# STM32H743.net
KiCad netlist of a schematic drawn in Altium Designer
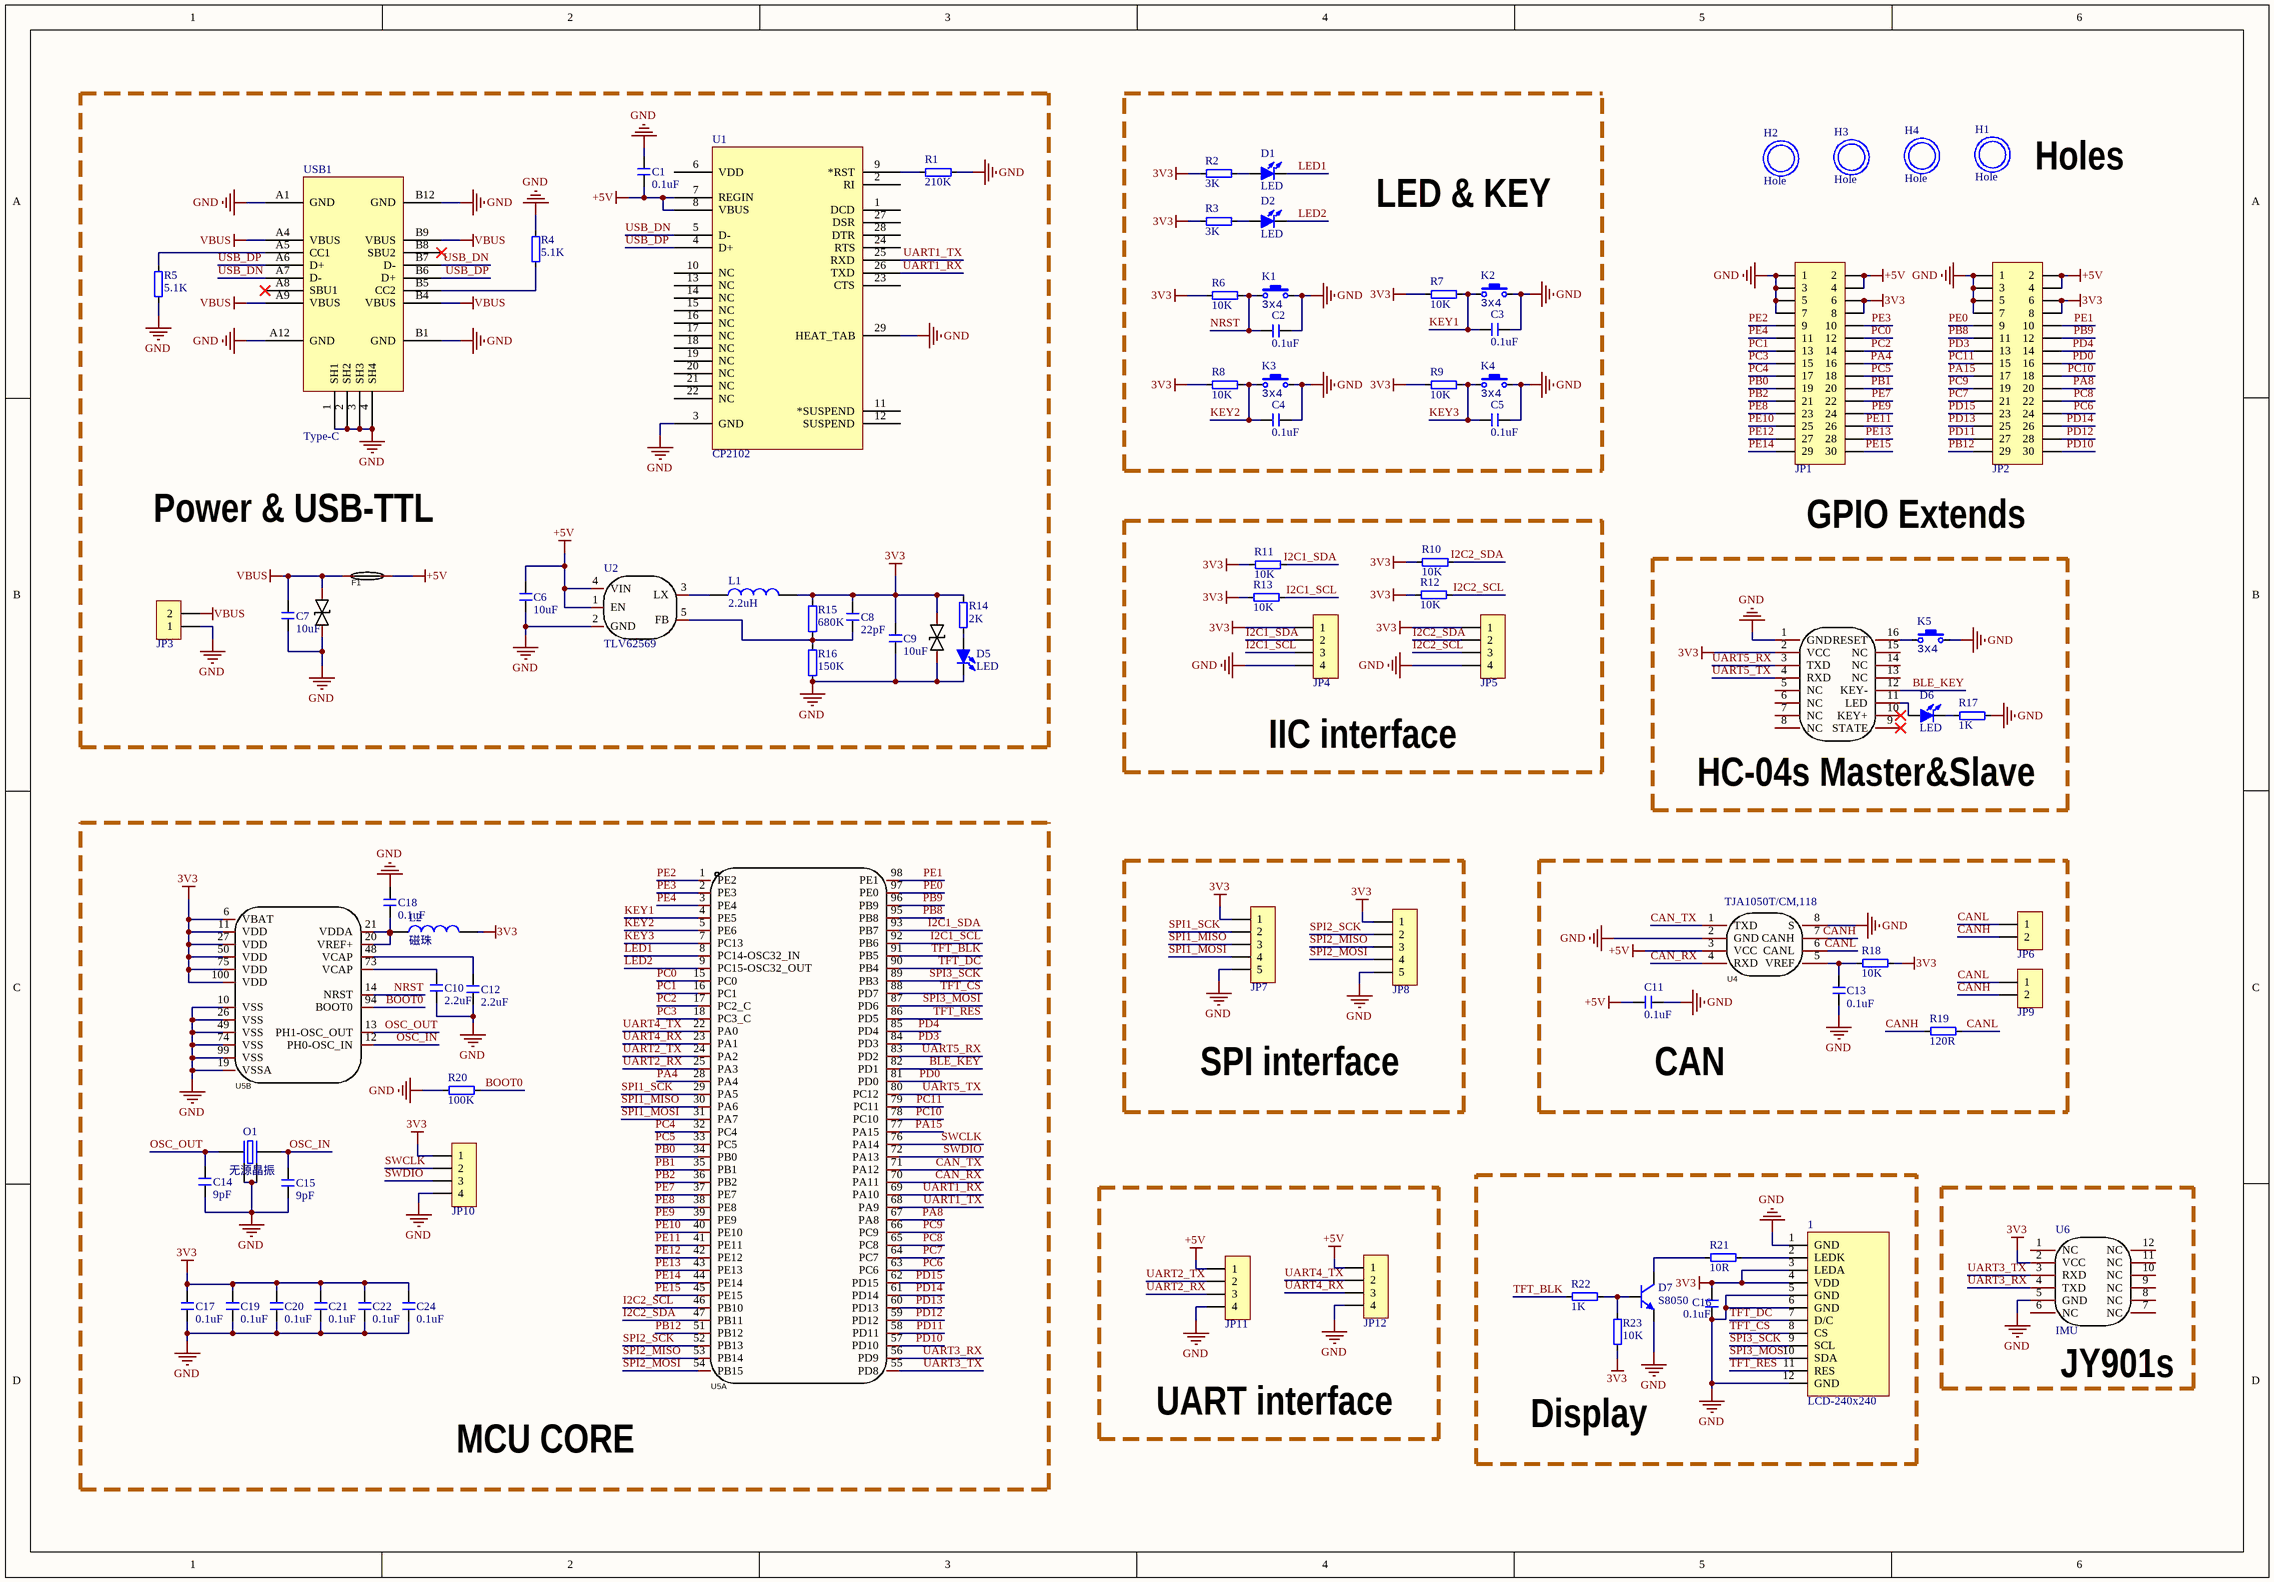
[diagram p0: STM32H743_原理图.SchDoc]

(export (version "E")
  (design (tool "Eeschema 10.0.6"))
  (components
    (comp (ref "1")
      (value "LCD-240x240")
      (footprint "LCD-240x240-NoHole")
      (description "显示屏")
      (libsource (lib "STM32H743原理图库") (part "LCD-240x240"))
    )
    (comp (ref "C1") (value "0.1uF") (footprint "CAP_0402") (libsource (lib "IntLib") (part "Capacitor")))
    (comp (ref "C2") (value "0.1uF") (footprint "CAP_0402") (libsource (lib "IntLib") (part "Capacitor")))
    (comp (ref "C3") (value "0.1uF") (footprint "CAP_0402") (libsource (lib "IntLib") (part "Capacitor")))
    (comp (ref "C4") (value "0.1uF") (footprint "CAP_0402") (libsource (lib "IntLib") (part "Capacitor")))
    (comp (ref "C5") (value "0.1uF") (footprint "CAP_0402") (libsource (lib "IntLib") (part "Capacitor")))
    (comp (ref "C6") (value "10uF") (footprint "CAP_0402") (libsource (lib "IntLib") (part "Capacitor")))
    (comp (ref "C7") (value "10uF") (footprint "CAP_0402") (libsource (lib "IntLib") (part "Capacitor")))
    (comp (ref "C8") (value "22pF") (footprint "CAP_0402") (libsource (lib "IntLib") (part "Capacitor")))
    (comp (ref "C9") (value "10uF") (footprint "CAP_0402") (libsource (lib "IntLib") (part "Capacitor")))
    (comp (ref "C10") (value "2.2uF") (footprint "CAP_0402") (libsource (lib "IntLib") (part "Capacitor")))
    (comp (ref "C11") (value "0.1uF") (footprint "CAP_0402") (libsource (lib "IntLib") (part "Capacitor")))
    (comp (ref "C12") (value "2.2uF") (footprint "CAP_0402") (libsource (lib "IntLib") (part "Capacitor")))
    (comp (ref "C13") (value "0.1uF") (footprint "CAP_0402") (libsource (lib "IntLib") (part "Capacitor")))
    (comp (ref "C14") (value "9pF") (footprint "CAP_0402") (libsource (lib "IntLib") (part "Capacitor")))
    (comp (ref "C15") (value "9pF") (footprint "CAP_0402") (libsource (lib "IntLib") (part "Capacitor")))
    (comp (ref "C16") (value "0.1uF") (footprint "CAP_0402") (libsource (lib "IntLib") (part "Capacitor")))
    (comp (ref "C17") (value "0.1uF") (footprint "CAP_0402") (libsource (lib "IntLib") (part "Capacitor")))
    (comp (ref "C18") (value "0.1uF") (footprint "CAP_0402") (libsource (lib "IntLib") (part "Capacitor")))
    (comp (ref "C19") (value "0.1uF") (footprint "CAP_0402") (libsource (lib "IntLib") (part "Capacitor")))
    (comp (ref "C20") (value "0.1uF") (footprint "CAP_0402") (libsource (lib "IntLib") (part "Capacitor")))
    (comp (ref "C21") (value "0.1uF") (footprint "CAP_0402") (libsource (lib "IntLib") (part "Capacitor")))
    (comp (ref "C22") (value "0.1uF") (footprint "CAP_0402") (libsource (lib "IntLib") (part "Capacitor")))
    (comp (ref "C24") (value "0.1uF") (footprint "CAP_0402") (libsource (lib "IntLib") (part "Capacitor")))
    (comp (ref "D1") (value "LED") (footprint "LED_0402_RED") (libsource (lib "IntLib") (part "LED")))
    (comp (ref "D2") (value "LED") (footprint "LED_0402_RED") (libsource (lib "IntLib") (part "LED")))
    (comp (ref "D3")
      (value "LESD3Z5.0CMT1G")
      (footprint "SOD-323")
      (fields (field (name "MANUFACTURER") "LRC(乐山无线电)"))
      (libsource (lib "STM32H743原理图库") (part "LESD3Z5.0CMT1G"))
    )
    (comp (ref "D4")
      (value "LESD3Z5.0CMT1G")
      (footprint "SOD-323")
      (fields (field (name "MANUFACTURER") "LRC(乐山无线电)"))
      (libsource (lib "STM32H743原理图库") (part "LESD3Z5.0CMT1G"))
    )
    (comp (ref "D5") (value "LED") (footprint "LED_0402_RED") (libsource (lib "IntLib") (part "LED")))
    (comp (ref "D6") (value "LED") (footprint "LED_0402_RED") (libsource (lib "IntLib") (part "LED")))
    (comp (ref "D7") (value "S8050") (footprint "SOT23-3L") (libsource (lib "IntLib") (part "三极管-NPN")))
    (comp (ref "F1")
      (value "S0603-F-2.0A")
      (footprint "R 0603")
      (fields (field (name "MANUFACTURER") "SART(萨特)"))
      (libsource (lib "STM32H743原理图库") (part "S0603-F-2.0A"))
    )
    (comp (ref "H1") (value "Hole") (footprint "Hole") (libsource (lib "IntLib") (part "Hole")))
    (comp (ref "H2") (value "Hole") (footprint "Hole") (libsource (lib "IntLib") (part "Hole")))
    (comp (ref "H3") (value "Hole") (footprint "Hole") (libsource (lib "IntLib") (part "Hole")))
    (comp (ref "H4") (value "Hole") (footprint "Hole") (libsource (lib "IntLib") (part "Hole")))
    (comp (ref "JP1")
      (value "Header 2X11")
      (footprint "HDR2.54-LI-2x15P")
      (description "15*2P接插件")
      (fields (field (name "版权归属") "源创客"))
      (libsource (lib "STM32H743原理图库") (part "Header 15X2"))
    )
    (comp (ref "JP2")
      (value "Header 2X11")
      (footprint "HDR2.54-LI-2x15P")
      (description "15*2P接插件")
      (fields (field (name "版权归属") "源创客"))
      (libsource (lib "STM32H743原理图库") (part "Header 15X2"))
    )
    (comp (ref "JP3")
      (value "HDR-1X2")
      (footprint "HDR2.54-LI-2P")
      (description "2P接插件")
      (fields (field (name "版权归属") "源创客"))
      (libsource (lib "") (part "Header 2_1"))
    )
    (comp (ref "JP4")
      (value "HDR-1X4")
      (footprint "MX 1.25-WS-4P")
      (description "4P接插件")
      (fields (field (name "版权归属") "源创客"))
      (libsource (lib "STM32H743原理图库") (part "Header 4"))
    )
    (comp (ref "JP5")
      (value "HDR-1X4")
      (footprint "MX 1.25-WS-4P")
      (description "4P接插件")
      (fields (field (name "版权归属") "源创客"))
      (libsource (lib "STM32H743原理图库") (part "Header 4"))
    )
    (comp (ref "JP6")
      (value "HDR-1X2")
      (footprint "GH1.25-WT-2P")
      (description "2P接插件")
      (fields (field (name "版权归属") "源创客"))
      (libsource (lib "STM32H743原理图库") (part "Header 2"))
    )
    (comp (ref "JP7")
      (value "HDR-1X5")
      (footprint "MX 1.25-WS-5P")
      (description "5P接插件")
      (fields (field (name "版权归属") "源创客"))
      (libsource (lib "STM32H743原理图库") (part "Header 5"))
    )
    (comp (ref "JP8")
      (value "HDR-1X5")
      (footprint "MX 1.25-WS-5P")
      (description "5P接插件")
      (fields (field (name "版权归属") "源创客"))
      (libsource (lib "STM32H743原理图库") (part "Header 5"))
    )
    (comp (ref "JP9")
      (value "HDR-1X2")
      (footprint "GH1.25-WT-2P")
      (description "2P接插件")
      (fields (field (name "版权归属") "源创客"))
      (libsource (lib "STM32H743原理图库") (part "Header 2"))
    )
    (comp (ref "JP10")
      (value "HDR-1X4")
      (footprint "MX 1.25-WS-4P")
      (description "4P接插件")
      (fields (field (name "版权归属") "源创客"))
      (libsource (lib "STM32H743原理图库") (part "Header 4"))
    )
    (comp (ref "JP11")
      (value "HDR-1X4")
      (footprint "MX 1.25-WS-4P")
      (description "4P接插件")
      (fields (field (name "版权归属") "源创客"))
      (libsource (lib "STM32H743原理图库") (part "Header 4"))
    )
    (comp (ref "JP12")
      (value "HDR-1X4")
      (footprint "MX 1.25-WS-4P")
      (description "4P接插件")
      (fields (field (name "版权归属") "源创客"))
      (libsource (lib "STM32H743原理图库") (part "Header 4"))
    )
    (comp (ref "K1")
      (value "3x4")
      (footprint "KEY")
      (description "Button")
      (fields (field (name "Comment") "TACT 2P"))
      (libsource (lib "STM32H743原理图库") (part "ButtonTACT_3x4x2_180"))
    )
    (comp (ref "K2")
      (value "3x4")
      (footprint "KEY")
      (description "Button")
      (fields (field (name "Comment") "TACT 2P"))
      (libsource (lib "STM32H743原理图库") (part "ButtonTACT_3x4x2_180"))
    )
    (comp (ref "K3")
      (value "3x4")
      (footprint "KEY")
      (description "Button")
      (fields (field (name "Comment") "TACT 2P"))
      (libsource (lib "STM32H743原理图库") (part "ButtonTACT_3x4x2_180"))
    )
    (comp (ref "K4")
      (value "3x4")
      (footprint "KEY")
      (description "Button")
      (fields (field (name "Comment") "TACT 2P"))
      (libsource (lib "STM32H743原理图库") (part "ButtonTACT_3x4x2_180"))
    )
    (comp (ref "K5")
      (value "3x4")
      (footprint "KEY")
      (description "Button")
      (fields (field (name "Comment") "TACT 2P"))
      (libsource (lib "STM32H743原理图库") (part "ButtonTACT_3x4x2_180"))
    )
    (comp (ref "L1") (value "2.2uH") (footprint "2520-L") (libsource (lib "IntLib") (part "Inductance")))
    (comp (ref "L2") (value "磁珠") (footprint "L 0603") (libsource (lib "IntLib") (part "Inductance")))
    (comp (ref "O1") (value "无源晶振") (footprint "OSC 3225-4P") (libsource (lib "STM32H743原理图库") (part "无源晶振")))
    (comp (ref "R1") (value "210K") (footprint "RES_0402") (libsource (lib "IntLib") (part "Resistor")))
    (comp (ref "R2") (value "3K") (footprint "RES_0402") (libsource (lib "IntLib") (part "Resistor")))
    (comp (ref "R3") (value "3K") (footprint "RES_0402") (libsource (lib "IntLib") (part "Resistor")))
    (comp (ref "R4") (value "5.1K") (footprint "RES_0402") (libsource (lib "IntLib") (part "Resistor")))
    (comp (ref "R5") (value "5.1K") (footprint "RES_0402") (libsource (lib "IntLib") (part "Resistor")))
    (comp (ref "R6") (value "10K") (footprint "RES_0402") (libsource (lib "IntLib") (part "Resistor")))
    (comp (ref "R7") (value "10K") (footprint "RES_0402") (libsource (lib "IntLib") (part "Resistor")))
    (comp (ref "R8") (value "10K") (footprint "RES_0402") (libsource (lib "IntLib") (part "Resistor")))
    (comp (ref "R9") (value "10K") (footprint "RES_0402") (libsource (lib "IntLib") (part "Resistor")))
    (comp (ref "R10") (value "10K") (footprint "RES_0402") (libsource (lib "IntLib") (part "Resistor")))
    (comp (ref "R11") (value "10K") (footprint "RES_0402") (libsource (lib "IntLib") (part "Resistor")))
    (comp (ref "R12") (value "10K") (footprint "RES_0402") (libsource (lib "IntLib") (part "Resistor")))
    (comp (ref "R13") (value "10K") (footprint "RES_0402") (libsource (lib "IntLib") (part "Resistor")))
    (comp (ref "R14") (value "2K") (footprint "RES_0402") (libsource (lib "IntLib") (part "Resistor")))
    (comp (ref "R15") (value "680K") (footprint "RES_0402") (libsource (lib "IntLib") (part "Resistor")))
    (comp (ref "R16") (value "150K") (footprint "RES_0402") (libsource (lib "IntLib") (part "Resistor")))
    (comp (ref "R17") (value "1K") (footprint "RES_0402") (libsource (lib "IntLib") (part "Resistor")))
    (comp (ref "R18") (value "10K") (footprint "RES_0402") (libsource (lib "IntLib") (part "Resistor")))
    (comp (ref "R19") (value "120R") (footprint "RES_0402") (libsource (lib "IntLib") (part "Resistor")))
    (comp (ref "R20") (value "100K") (footprint "RES_0402") (libsource (lib "IntLib") (part "Resistor")))
    (comp (ref "R21") (value "10R") (footprint "RES_0402") (libsource (lib "IntLib") (part "Resistor")))
    (comp (ref "R22") (value "1K") (footprint "RES_0402") (libsource (lib "IntLib") (part "Resistor")))
    (comp (ref "R23") (value "10K") (footprint "RES_0402") (libsource (lib "IntLib") (part "Resistor")))
    (comp (ref "U1")
      (value "CP2102")
      (footprint "QFN-28")
      (description "USB转TTL")
      (libsource (lib "STM32H743原理图库") (part "CP2102"))
    )
    (comp (ref "U2")
      (value "TLV62569")
      (footprint "SOT23-5N")
      (libsource (lib "STM32H743原理图库") (part "TLV62569"))
    )
    (comp (ref "U3")
      (value "TJA1050T/CM,118")
      (footprint "HC-04-S")
      (fields (field (name "MANUFACTURER") "NXP(恩智浦)"))
      (libsource (lib "STM32H743原理图库") (part "HC-04-S"))
    )
    (comp (ref "U4")
      (value "TJA1050T/CM,118")
      (footprint "SOP8")
      (fields (field (name "MANUFACTURER") "NXP(恩智浦)"))
      (libsource (lib "STM32H743原理图库") (part "TJA1050T/CM,118"))
    )
    (comp (ref "U5")
      (value "STM32H743VIT6_C114409")
      (footprint "LQFP100-14*14")
      (fields (field (name "MANUFACTURER") "ST(意法半导体)") (field (name "MANUFACTURER PART") "STM32H743VIT6"))
      (libsource (lib "STM32H743原理图库") (part "STM32H743VIT6_C114409"))
    )
    (comp (ref "U6") (value "IMU") (footprint "IMU") (libsource (lib "STM32H743原理图库") (part "IMU")))
    (comp (ref "USB1")
      (value "Type-C")
      (footprint "Type-C-TOP")
      (libsource (lib "STM32H743原理图库") (part "USB-Type-C-TOP"))
    )
  )
  (nets
    (net (code "1") (name "+5V") (class "Default")
      (node (ref "C1") (pin "1") (pinfunction "1_1") (pintype "passive"))
      (node (ref "C11") (pin "2") (pinfunction "2_2") (pintype "passive"))
      (node (ref "C6") (pin "2") (pinfunction "2_2") (pintype "passive"))
      (node (ref "F1") (pin "2") (pinfunction "2_2") (pintype "passive"))
      (node (ref "JP1") (pin "2") (pinfunction "2_2") (pintype "passive"))
      (node (ref "JP1") (pin "4") (pinfunction "4_4") (pintype "passive"))
      (node (ref "JP11") (pin "1") (pinfunction "1_1") (pintype "passive"))
      (node (ref "JP12") (pin "1") (pinfunction "1_1") (pintype "passive"))
      (node (ref "JP2") (pin "2") (pinfunction "2_2") (pintype "passive"))
      (node (ref "JP2") (pin "4") (pinfunction "4_4") (pintype "passive"))
      (node (ref "U1") (pin "7") (pinfunction "REGIN_7") (pintype "passive"))
      (node (ref "U1") (pin "8") (pinfunction "VBUS_8") (pintype "passive"))
      (node (ref "U2") (pin "1") (pinfunction "EN_1") (pintype "passive"))
      (node (ref "U2") (pin "4") (pinfunction "VIN_4") (pintype "passive"))
      (node (ref "U4") (pin "3") (pinfunction "VCC_3") (pintype "passive"))
    )
    (net (code "2") (name "/BLE_KEY") (class "Default")
      (node (ref "U3") (pin "12") (pinfunction "KEY-_12") (pintype "passive"))
      (node (ref "U5") (pin "82") (pinfunction "PD1_82") (pintype "passive"))
    )
    (net (code "3") (name "/BOOT0") (class "Default")
      (node (ref "R20") (pin "1") (pinfunction "1_1") (pintype "passive"))
      (node (ref "U5") (pin "94") (pinfunction "BOOT0_94") (pintype "passive"))
    )
    (net (code "4") (name "/CANH") (class "Default")
      (node (ref "JP6") (pin "2") (pinfunction "2_2") (pintype "passive"))
      (node (ref "JP9") (pin "2") (pinfunction "2_2") (pintype "passive"))
      (node (ref "R19") (pin "2") (pinfunction "2_2") (pintype "passive"))
      (node (ref "U4") (pin "7") (pinfunction "CANH_7") (pintype "passive"))
    )
    (net (code "5") (name "/CANL") (class "Default")
      (node (ref "JP6") (pin "1") (pinfunction "1_1") (pintype "passive"))
      (node (ref "JP9") (pin "1") (pinfunction "1_1") (pintype "passive"))
      (node (ref "R19") (pin "1") (pinfunction "1_1") (pintype "passive"))
      (node (ref "U4") (pin "6") (pinfunction "CANL_6") (pintype "passive"))
    )
    (net (code "6") (name "/CAN_RX") (class "Default")
      (node (ref "U4") (pin "4") (pinfunction "RXD_4") (pintype "passive"))
      (node (ref "U5") (pin "70") (pinfunction "PA11_70") (pintype "passive"))
    )
    (net (code "7") (name "/CAN_TX") (class "Default")
      (node (ref "U4") (pin "1") (pinfunction "TXD_1") (pintype "passive"))
      (node (ref "U5") (pin "71") (pinfunction "PA12_71") (pintype "passive"))
    )
    (net (code "8") (name "/I2C1_SCL") (class "Default")
      (node (ref "JP4") (pin "3") (pinfunction "3_3") (pintype "passive"))
      (node (ref "R13") (pin "1") (pinfunction "1_1") (pintype "passive"))
      (node (ref "U5") (pin "92") (pinfunction "PB6_92") (pintype "passive"))
    )
    (net (code "9") (name "/I2C1_SDA") (class "Default")
      (node (ref "JP4") (pin "2") (pinfunction "2_2") (pintype "passive"))
      (node (ref "R11") (pin "1") (pinfunction "1_1") (pintype "passive"))
      (node (ref "U5") (pin "93") (pinfunction "PB7_93") (pintype "passive"))
    )
    (net (code "10") (name "/I2C2_SCL") (class "Default")
      (node (ref "JP5") (pin "3") (pinfunction "3_3") (pintype "passive"))
      (node (ref "R12") (pin "1") (pinfunction "1_1") (pintype "passive"))
      (node (ref "U5") (pin "46") (pinfunction "PB10_46") (pintype "passive"))
    )
    (net (code "11") (name "/I2C2_SDA") (class "Default")
      (node (ref "JP5") (pin "2") (pinfunction "2_2") (pintype "passive"))
      (node (ref "R10") (pin "1") (pinfunction "1_1") (pintype "passive"))
      (node (ref "U5") (pin "47") (pinfunction "PB11_47") (pintype "passive"))
    )
    (net (code "12") (name "/KEY1") (class "Default")
      (node (ref "C3") (pin "2") (pinfunction "2_2") (pintype "passive"))
      (node (ref "K2") (pin "1") (pinfunction "1_1") (pintype "passive"))
      (node (ref "R7") (pin "1") (pinfunction "1_1") (pintype "passive"))
      (node (ref "U5") (pin "4") (pinfunction "PE5_4") (pintype "passive"))
    )
    (net (code "13") (name "/KEY2") (class "Default")
      (node (ref "C4") (pin "2") (pinfunction "2_2") (pintype "passive"))
      (node (ref "K3") (pin "1") (pinfunction "1_1") (pintype "passive"))
      (node (ref "R8") (pin "1") (pinfunction "1_1") (pintype "passive"))
      (node (ref "U5") (pin "5") (pinfunction "PE6_5") (pintype "passive"))
    )
    (net (code "14") (name "/KEY3") (class "Default")
      (node (ref "C5") (pin "2") (pinfunction "2_2") (pintype "passive"))
      (node (ref "K4") (pin "1") (pinfunction "1_1") (pintype "passive"))
      (node (ref "R9") (pin "1") (pinfunction "1_1") (pintype "passive"))
      (node (ref "U5") (pin "7") (pinfunction "PC13_7") (pintype "passive"))
    )
    (net (code "15") (name "/LED1") (class "Default")
      (node (ref "D1") (pin "2") (pinfunction "K_2") (pintype "passive"))
      (node (ref "U5") (pin "8") (pinfunction "PC14-OSC32_IN_8") (pintype "passive"))
    )
    (net (code "16") (name "/LED2") (class "Default")
      (node (ref "D2") (pin "2") (pinfunction "K_2") (pintype "passive"))
      (node (ref "U5") (pin "9") (pinfunction "PC15-OSC32_OUT_9") (pintype "passive"))
    )
    (net (code "17") (name "/NRST") (class "Default")
      (node (ref "C2") (pin "2") (pinfunction "2_2") (pintype "passive"))
      (node (ref "K1") (pin "1") (pinfunction "1_1") (pintype "passive"))
      (node (ref "R6") (pin "1") (pinfunction "1_1") (pintype "passive"))
      (node (ref "U5") (pin "14") (pinfunction "NRST_14") (pintype "passive"))
    )
    (net (code "18") (name "/OSC_IN") (class "Default")
      (node (ref "C15") (pin "2") (pinfunction "2_2") (pintype "passive"))
      (node (ref "O1") (pin "3") (pinfunction "3_3") (pintype "passive"))
      (node (ref "U5") (pin "12") (pinfunction "PH0-OSC_IN_12") (pintype "passive"))
    )
    (net (code "19") (name "/OSC_OUT") (class "Default")
      (node (ref "C14") (pin "2") (pinfunction "2_2") (pintype "passive"))
      (node (ref "O1") (pin "1") (pinfunction "1_1") (pintype "passive"))
      (node (ref "U5") (pin "13") (pinfunction "PH1-OSC_OUT_13") (pintype "passive"))
    )
    (net (code "20") (name "/PA4") (class "Default")
      (node (ref "JP1") (pin "16") (pinfunction "16_16") (pintype "passive"))
      (node (ref "U5") (pin "28") (pinfunction "PA4_28") (pintype "passive"))
    )
    (net (code "21") (name "/PA8") (class "Default")
      (node (ref "JP2") (pin "20") (pinfunction "20_20") (pintype "passive"))
      (node (ref "U5") (pin "67") (pinfunction "PA8_67") (pintype "passive"))
    )
    (net (code "22") (name "/PA15") (class "Default")
      (node (ref "JP2") (pin "17") (pinfunction "17_17") (pintype "passive"))
      (node (ref "U5") (pin "77") (pinfunction "PA15_77") (pintype "passive"))
    )
    (net (code "23") (name "/PB0") (class "Default")
      (node (ref "JP1") (pin "19") (pinfunction "19_19") (pintype "passive"))
      (node (ref "U5") (pin "34") (pinfunction "PB0_34") (pintype "passive"))
    )
    (net (code "24") (name "/PB1") (class "Default")
      (node (ref "JP1") (pin "20") (pinfunction "20_20") (pintype "passive"))
      (node (ref "U5") (pin "35") (pinfunction "PB1_35") (pintype "passive"))
    )
    (net (code "25") (name "/PB2") (class "Default")
      (node (ref "JP1") (pin "21") (pinfunction "21_21") (pintype "passive"))
      (node (ref "U5") (pin "36") (pinfunction "PB2_36") (pintype "passive"))
    )
    (net (code "26") (name "/PB8") (class "Default")
      (node (ref "JP2") (pin "11") (pinfunction "11_11") (pintype "passive"))
      (node (ref "U5") (pin "95") (pinfunction "PB8_95") (pintype "passive"))
    )
    (net (code "27") (name "/PB9") (class "Default")
      (node (ref "JP2") (pin "12") (pinfunction "12_12") (pintype "passive"))
      (node (ref "U5") (pin "96") (pinfunction "PB9_96") (pintype "passive"))
    )
    (net (code "28") (name "/PB12") (class "Default")
      (node (ref "JP2") (pin "29") (pinfunction "29_29") (pintype "passive"))
      (node (ref "U5") (pin "51") (pinfunction "PB12_51") (pintype "passive"))
    )
    (net (code "29") (name "/PC0") (class "Default")
      (node (ref "JP1") (pin "12") (pinfunction "12_12") (pintype "passive"))
      (node (ref "U5") (pin "15") (pinfunction "PC0_15") (pintype "passive"))
    )
    (net (code "30") (name "/PC1") (class "Default")
      (node (ref "JP1") (pin "13") (pinfunction "13_13") (pintype "passive"))
      (node (ref "U5") (pin "16") (pinfunction "PC1_16") (pintype "passive"))
    )
    (net (code "31") (name "/PC2") (class "Default")
      (node (ref "JP1") (pin "14") (pinfunction "14_14") (pintype "passive"))
      (node (ref "U5") (pin "17") (pinfunction "PC2_C_17") (pintype "passive"))
    )
    (net (code "32") (name "/PC3") (class "Default")
      (node (ref "JP1") (pin "15") (pinfunction "15_15") (pintype "passive"))
      (node (ref "U5") (pin "18") (pinfunction "PC3_C_18") (pintype "passive"))
    )
    (net (code "33") (name "/PC4") (class "Default")
      (node (ref "JP1") (pin "17") (pinfunction "17_17") (pintype "passive"))
      (node (ref "U5") (pin "32") (pinfunction "PC4_32") (pintype "passive"))
    )
    (net (code "34") (name "/PC5") (class "Default")
      (node (ref "JP1") (pin "18") (pinfunction "18_18") (pintype "passive"))
      (node (ref "U5") (pin "33") (pinfunction "PC5_33") (pintype "passive"))
    )
    (net (code "35") (name "/PC6") (class "Default")
      (node (ref "JP2") (pin "24") (pinfunction "24_24") (pintype "passive"))
      (node (ref "U5") (pin "63") (pinfunction "PC6_63") (pintype "passive"))
    )
    (net (code "36") (name "/PC7") (class "Default")
      (node (ref "JP2") (pin "21") (pinfunction "21_21") (pintype "passive"))
      (node (ref "U5") (pin "64") (pinfunction "PC7_64") (pintype "passive"))
    )
    (net (code "37") (name "/PC8") (class "Default")
      (node (ref "JP2") (pin "22") (pinfunction "22_22") (pintype "passive"))
      (node (ref "U5") (pin "65") (pinfunction "PC8_65") (pintype "passive"))
    )
    (net (code "38") (name "/PC9") (class "Default")
      (node (ref "JP2") (pin "19") (pinfunction "19_19") (pintype "passive"))
      (node (ref "U5") (pin "66") (pinfunction "PC9_66") (pintype "passive"))
    )
    (net (code "39") (name "/PC10") (class "Default")
      (node (ref "JP2") (pin "18") (pinfunction "18_18") (pintype "passive"))
      (node (ref "U5") (pin "78") (pinfunction "PC10_78") (pintype "passive"))
    )
    (net (code "40") (name "/PC11") (class "Default")
      (node (ref "JP2") (pin "15") (pinfunction "15_15") (pintype "passive"))
      (node (ref "U5") (pin "79") (pinfunction "PC11_79") (pintype "passive"))
    )
    (net (code "41") (name "/PD0") (class "Default")
      (node (ref "JP2") (pin "16") (pinfunction "16_16") (pintype "passive"))
      (node (ref "U5") (pin "81") (pinfunction "PD0_81") (pintype "passive"))
    )
    (net (code "42") (name "/PD3") (class "Default")
      (node (ref "JP2") (pin "13") (pinfunction "13_13") (pintype "passive"))
      (node (ref "U5") (pin "84") (pinfunction "PD3_84") (pintype "passive"))
    )
    (net (code "43") (name "/PD4") (class "Default")
      (node (ref "JP2") (pin "14") (pinfunction "14_14") (pintype "passive"))
      (node (ref "U5") (pin "85") (pinfunction "PD4_85") (pintype "passive"))
    )
    (net (code "44") (name "/PD10") (class "Default")
      (node (ref "JP2") (pin "30") (pinfunction "30_30") (pintype "passive"))
      (node (ref "U5") (pin "57") (pinfunction "PD10_57") (pintype "passive"))
    )
    (net (code "45") (name "/PD11") (class "Default")
      (node (ref "JP2") (pin "27") (pinfunction "27_27") (pintype "passive"))
      (node (ref "U5") (pin "58") (pinfunction "PD11_58") (pintype "passive"))
    )
    (net (code "46") (name "/PD12") (class "Default")
      (node (ref "JP2") (pin "28") (pinfunction "28_28") (pintype "passive"))
      (node (ref "U5") (pin "59") (pinfunction "PD12_59") (pintype "passive"))
    )
    (net (code "47") (name "/PD13") (class "Default")
      (node (ref "JP2") (pin "25") (pinfunction "25_25") (pintype "passive"))
      (node (ref "U5") (pin "60") (pinfunction "PD13_60") (pintype "passive"))
    )
    (net (code "48") (name "/PD14") (class "Default")
      (node (ref "JP2") (pin "26") (pinfunction "26_26") (pintype "passive"))
      (node (ref "U5") (pin "61") (pinfunction "PD14_61") (pintype "passive"))
    )
    (net (code "49") (name "/PD15") (class "Default")
      (node (ref "JP2") (pin "23") (pinfunction "23_23") (pintype "passive"))
      (node (ref "U5") (pin "62") (pinfunction "PD15_62") (pintype "passive"))
    )
    (net (code "50") (name "/PE0") (class "Default")
      (node (ref "JP2") (pin "9") (pinfunction "9_9") (pintype "passive"))
      (node (ref "U5") (pin "97") (pinfunction "PE0_97") (pintype "passive"))
    )
    (net (code "51") (name "/PE1") (class "Default")
      (node (ref "JP2") (pin "10") (pinfunction "10_10") (pintype "passive"))
      (node (ref "U5") (pin "98") (pinfunction "PE1_98") (pintype "passive"))
    )
    (net (code "52") (name "/PE2") (class "Default")
      (node (ref "JP1") (pin "9") (pinfunction "9_9") (pintype "passive"))
      (node (ref "U5") (pin "1") (pinfunction "PE2_1") (pintype "passive"))
    )
    (net (code "53") (name "/PE3") (class "Default")
      (node (ref "JP1") (pin "10") (pinfunction "10_10") (pintype "passive"))
      (node (ref "U5") (pin "2") (pinfunction "PE3_2") (pintype "passive"))
    )
    (net (code "54") (name "/PE4") (class "Default")
      (node (ref "JP1") (pin "11") (pinfunction "11_11") (pintype "passive"))
      (node (ref "U5") (pin "3") (pinfunction "PE4_3") (pintype "passive"))
    )
    (net (code "55") (name "/PE7") (class "Default")
      (node (ref "JP1") (pin "22") (pinfunction "22_22") (pintype "passive"))
      (node (ref "U5") (pin "37") (pinfunction "PE7_37") (pintype "passive"))
    )
    (net (code "56") (name "/PE8") (class "Default")
      (node (ref "JP1") (pin "23") (pinfunction "23_23") (pintype "passive"))
      (node (ref "U5") (pin "38") (pinfunction "PE8_38") (pintype "passive"))
    )
    (net (code "57") (name "/PE9") (class "Default")
      (node (ref "JP1") (pin "24") (pinfunction "24_24") (pintype "passive"))
      (node (ref "U5") (pin "39") (pinfunction "PE9_39") (pintype "passive"))
    )
    (net (code "58") (name "/PE10") (class "Default")
      (node (ref "JP1") (pin "25") (pinfunction "25_25") (pintype "passive"))
      (node (ref "U5") (pin "40") (pinfunction "PE10_40") (pintype "passive"))
    )
    (net (code "59") (name "/PE11") (class "Default")
      (node (ref "JP1") (pin "26") (pinfunction "26_26") (pintype "passive"))
      (node (ref "U5") (pin "41") (pinfunction "PE11_41") (pintype "passive"))
    )
    (net (code "60") (name "/PE12") (class "Default")
      (node (ref "JP1") (pin "27") (pinfunction "27_27") (pintype "passive"))
      (node (ref "U5") (pin "42") (pinfunction "PE12_42") (pintype "passive"))
    )
    (net (code "61") (name "/PE13") (class "Default")
      (node (ref "JP1") (pin "28") (pinfunction "28_28") (pintype "passive"))
      (node (ref "U5") (pin "43") (pinfunction "PE13_43") (pintype "passive"))
    )
    (net (code "62") (name "/PE14") (class "Default")
      (node (ref "JP1") (pin "29") (pinfunction "29_29") (pintype "passive"))
      (node (ref "U5") (pin "44") (pinfunction "PE14_44") (pintype "passive"))
    )
    (net (code "63") (name "/PE15") (class "Default")
      (node (ref "JP1") (pin "30") (pinfunction "30_30") (pintype "passive"))
      (node (ref "U5") (pin "45") (pinfunction "PE15_45") (pintype "passive"))
    )
    (net (code "64") (name "/SPI1_MISO") (class "Default")
      (node (ref "JP7") (pin "3") (pinfunction "3_3") (pintype "passive"))
      (node (ref "U5") (pin "30") (pinfunction "PA6_30") (pintype "passive"))
    )
    (net (code "65") (name "/SPI1_MOSI") (class "Default")
      (node (ref "JP7") (pin "4") (pinfunction "4_4") (pintype "passive"))
      (node (ref "U5") (pin "31") (pinfunction "PA7_31") (pintype "passive"))
    )
    (net (code "66") (name "/SPI1_SCK") (class "Default")
      (node (ref "JP7") (pin "2") (pinfunction "2_2") (pintype "passive"))
      (node (ref "U5") (pin "29") (pinfunction "PA5_29") (pintype "passive"))
    )
    (net (code "67") (name "/SPI2_MISO") (class "Default")
      (node (ref "JP8") (pin "3") (pinfunction "3_3") (pintype "passive"))
      (node (ref "U5") (pin "53") (pinfunction "PB14_53") (pintype "passive"))
    )
    (net (code "68") (name "/SPI2_MOSI") (class "Default")
      (node (ref "JP8") (pin "4") (pinfunction "4_4") (pintype "passive"))
      (node (ref "U5") (pin "54") (pinfunction "PB15_54") (pintype "passive"))
    )
    (net (code "69") (name "/SPI2_SCK") (class "Default")
      (node (ref "JP8") (pin "2") (pinfunction "2_2") (pintype "passive"))
      (node (ref "U5") (pin "52") (pinfunction "PB13_52") (pintype "passive"))
    )
    (net (code "70") (name "/SPI3_MOSI") (class "Default")
      (node (ref "1") (pin "10") (pinfunction "SDA_10") (pintype "passive"))
      (node (ref "U5") (pin "87") (pinfunction "PD6_87") (pintype "passive"))
    )
    (net (code "71") (name "/SPI3_SCK") (class "Default")
      (node (ref "1") (pin "9") (pinfunction "SCL_9") (pintype "passive"))
      (node (ref "U5") (pin "89") (pinfunction "PB3_89") (pintype "passive"))
    )
    (net (code "72") (name "/SWCLK") (class "Default")
      (node (ref "JP10") (pin "2") (pinfunction "2_2") (pintype "passive"))
      (node (ref "U5") (pin "76") (pinfunction "PA14_76") (pintype "passive"))
    )
    (net (code "73") (name "/SWDIO") (class "Default")
      (node (ref "JP10") (pin "3") (pinfunction "3_3") (pintype "passive"))
      (node (ref "U5") (pin "72") (pinfunction "PA13_72") (pintype "passive"))
    )
    (net (code "74") (name "/TFT_BLK") (class "Default")
      (node (ref "R22") (pin "2") (pinfunction "2_2") (pintype "passive"))
      (node (ref "U5") (pin "91") (pinfunction "PB5_91") (pintype "passive"))
    )
    (net (code "75") (name "/TFT_CS") (class "Default")
      (node (ref "1") (pin "8") (pinfunction "CS_8") (pintype "passive"))
      (node (ref "U5") (pin "88") (pinfunction "PD7_88") (pintype "passive"))
    )
    (net (code "76") (name "/TFT_DC") (class "Default")
      (node (ref "1") (pin "7") (pinfunction "D/C_7") (pintype "passive"))
      (node (ref "U5") (pin "90") (pinfunction "PB4_90") (pintype "passive"))
    )
    (net (code "77") (name "/TFT_RES") (class "Default")
      (node (ref "1") (pin "11") (pinfunction "RES_11") (pintype "passive"))
      (node (ref "U5") (pin "86") (pinfunction "PD5_86") (pintype "passive"))
    )
    (net (code "78") (name "/UART1_RX") (class "Default")
      (node (ref "U1") (pin "26") (pinfunction "TXD_26") (pintype "passive"))
      (node (ref "U5") (pin "69") (pinfunction "PA10_69") (pintype "passive"))
    )
    (net (code "79") (name "/UART1_TX") (class "Default")
      (node (ref "U1") (pin "25") (pinfunction "RXD_25") (pintype "passive"))
      (node (ref "U5") (pin "68") (pinfunction "PA9_68") (pintype "passive"))
    )
    (net (code "80") (name "/UART2_RX") (class "Default")
      (node (ref "JP11") (pin "3") (pinfunction "3_3") (pintype "passive"))
      (node (ref "U5") (pin "25") (pinfunction "PA3_25") (pintype "passive"))
    )
    (net (code "81") (name "/UART2_TX") (class "Default")
      (node (ref "JP11") (pin "2") (pinfunction "2_2") (pintype "passive"))
      (node (ref "U5") (pin "24") (pinfunction "PA2_24") (pintype "passive"))
    )
    (net (code "82") (name "/UART3_RX") (class "Default")
      (node (ref "U5") (pin "56") (pinfunction "PD9_56") (pintype "passive"))
      (node (ref "U6") (pin "4") (pinfunction "TXD_4") (pintype "passive"))
    )
    (net (code "83") (name "/UART3_TX") (class "Default")
      (node (ref "U5") (pin "55") (pinfunction "PD8_55") (pintype "passive"))
      (node (ref "U6") (pin "3") (pinfunction "RXD_3") (pintype "passive"))
    )
    (net (code "84") (name "/UART4_RX") (class "Default")
      (node (ref "JP12") (pin "3") (pinfunction "3_3") (pintype "passive"))
      (node (ref "U5") (pin "23") (pinfunction "PA1_23") (pintype "passive"))
    )
    (net (code "85") (name "/UART4_TX") (class "Default")
      (node (ref "JP12") (pin "2") (pinfunction "2_2") (pintype "passive"))
      (node (ref "U5") (pin "22") (pinfunction "PA0_22") (pintype "passive"))
    )
    (net (code "86") (name "/UART5_RX") (class "Default")
      (node (ref "U3") (pin "3") (pinfunction "TXD_3") (pintype "passive"))
      (node (ref "U5") (pin "83") (pinfunction "PD2_83") (pintype "passive"))
    )
    (net (code "87") (name "/UART5_TX") (class "Default")
      (node (ref "U3") (pin "4") (pinfunction "RXD_4") (pintype "passive"))
      (node (ref "U5") (pin "80") (pinfunction "PC12_80") (pintype "passive"))
    )
    (net (code "88") (name "/USB_DN") (class "Default")
      (node (ref "U1") (pin "5") (pinfunction "D-_5") (pintype "passive"))
      (node (ref "USB1") (pin "A7") (pinfunction "D-_A7") (pintype "passive"))
      (node (ref "USB1") (pin "B7") (pinfunction "D-_B7") (pintype "passive"))
    )
    (net (code "89") (name "/USB_DP") (class "Default")
      (node (ref "U1") (pin "4") (pinfunction "D+_4") (pintype "passive"))
      (node (ref "USB1") (pin "A6") (pinfunction "D+_A6") (pintype "passive"))
      (node (ref "USB1") (pin "B6") (pinfunction "D+_B6") (pintype "passive"))
    )
    (net (code "90") (name "3V3") (class "Default")
      (node (ref "1") (pin "3") (pinfunction "LEDA_3") (pintype "passive"))
      (node (ref "1") (pin "4") (pinfunction "VDD_4") (pintype "passive"))
      (node (ref "C16") (pin "1") (pinfunction "1_1") (pintype "passive"))
      (node (ref "C17") (pin "2") (pinfunction "2_2") (pintype "passive"))
      (node (ref "C19") (pin "2") (pinfunction "2_2") (pintype "passive"))
      (node (ref "C20") (pin "2") (pinfunction "2_2") (pintype "passive"))
      (node (ref "C21") (pin "2") (pinfunction "2_2") (pintype "passive"))
      (node (ref "C22") (pin "2") (pinfunction "2_2") (pintype "passive"))
      (node (ref "C24") (pin "2") (pinfunction "2_2") (pintype "passive"))
      (node (ref "C8") (pin "2") (pinfunction "2_2") (pintype "passive"))
      (node (ref "C9") (pin "2") (pinfunction "2_2") (pintype "passive"))
      (node (ref "D4") (pin "2") (pinfunction "2_2") (pintype "passive"))
      (node (ref "JP1") (pin "6") (pinfunction "6_6") (pintype "passive"))
      (node (ref "JP1") (pin "8") (pinfunction "8_8") (pintype "passive"))
      (node (ref "JP10") (pin "1") (pinfunction "1_1") (pintype "passive"))
      (node (ref "JP2") (pin "6") (pinfunction "6_6") (pintype "passive"))
      (node (ref "JP2") (pin "8") (pinfunction "8_8") (pintype "passive"))
      (node (ref "JP4") (pin "1") (pinfunction "1_1") (pintype "passive"))
      (node (ref "JP5") (pin "1") (pinfunction "1_1") (pintype "passive"))
      (node (ref "JP7") (pin "1") (pinfunction "1_1") (pintype "passive"))
      (node (ref "JP8") (pin "1") (pinfunction "1_1") (pintype "passive"))
      (node (ref "L1") (pin "2") (pinfunction "2_2") (pintype "passive"))
      (node (ref "L2") (pin "2") (pinfunction "2_2") (pintype "passive"))
      (node (ref "R10") (pin "2") (pinfunction "2_2") (pintype "passive"))
      (node (ref "R11") (pin "2") (pinfunction "2_2") (pintype "passive"))
      (node (ref "R12") (pin "2") (pinfunction "2_2") (pintype "passive"))
      (node (ref "R13") (pin "2") (pinfunction "2_2") (pintype "passive"))
      (node (ref "R14") (pin "2") (pinfunction "2_2") (pintype "passive"))
      (node (ref "R15") (pin "2") (pinfunction "2_2") (pintype "passive"))
      (node (ref "R18") (pin "1") (pinfunction "1_1") (pintype "passive"))
      (node (ref "R2") (pin "2") (pinfunction "2_2") (pintype "passive"))
      (node (ref "R23") (pin "2") (pinfunction "2_2") (pintype "passive"))
      (node (ref "R3") (pin "2") (pinfunction "2_2") (pintype "passive"))
      (node (ref "R6") (pin "2") (pinfunction "2_2") (pintype "passive"))
      (node (ref "R7") (pin "2") (pinfunction "2_2") (pintype "passive"))
      (node (ref "R8") (pin "2") (pinfunction "2_2") (pintype "passive"))
      (node (ref "R9") (pin "2") (pinfunction "2_2") (pintype "passive"))
      (node (ref "U3") (pin "2") (pinfunction "VCC_2") (pintype "passive"))
      (node (ref "U5") (pin "100") (pinfunction "VDD_100") (pintype "passive"))
      (node (ref "U5") (pin "11") (pinfunction "VDD_11") (pintype "passive"))
      (node (ref "U5") (pin "27") (pinfunction "VDD_27") (pintype "passive"))
      (node (ref "U5") (pin "50") (pinfunction "VDD_50") (pintype "passive"))
      (node (ref "U5") (pin "6") (pinfunction "VBAT_6") (pintype "passive"))
      (node (ref "U5") (pin "75") (pinfunction "VDD_75") (pintype "passive"))
      (node (ref "U6") (pin "2") (pinfunction "VCC_2") (pintype "passive"))
    )
    (net (code "91") (name "GND") (class "Default")
      (node (ref "1") (pin "1") (pinfunction "GND_1") (pintype "passive"))
      (node (ref "1") (pin "12") (pinfunction "GND_12") (pintype "passive"))
      (node (ref "1") (pin "5") (pinfunction "GND_5") (pintype "passive"))
      (node (ref "1") (pin "6") (pinfunction "GND_6") (pintype "passive"))
      (node (ref "C1") (pin "2") (pinfunction "2_2") (pintype "passive"))
      (node (ref "C10") (pin "1") (pinfunction "1_1") (pintype "passive"))
      (node (ref "C11") (pin "1") (pinfunction "1_1") (pintype "passive"))
      (node (ref "C12") (pin "1") (pinfunction "1_1") (pintype "passive"))
      (node (ref "C13") (pin "2") (pinfunction "2_2") (pintype "passive"))
      (node (ref "C14") (pin "1") (pinfunction "1_1") (pintype "passive"))
      (node (ref "C15") (pin "1") (pinfunction "1_1") (pintype "passive"))
      (node (ref "C16") (pin "2") (pinfunction "2_2") (pintype "passive"))
      (node (ref "C17") (pin "1") (pinfunction "1_1") (pintype "passive"))
      (node (ref "C18") (pin "2") (pinfunction "2_2") (pintype "passive"))
      (node (ref "C19") (pin "1") (pinfunction "1_1") (pintype "passive"))
      (node (ref "C2") (pin "1") (pinfunction "1_1") (pintype "passive"))
      (node (ref "C20") (pin "1") (pinfunction "1_1") (pintype "passive"))
      (node (ref "C21") (pin "1") (pinfunction "1_1") (pintype "passive"))
      (node (ref "C22") (pin "1") (pinfunction "1_1") (pintype "passive"))
      (node (ref "C24") (pin "1") (pinfunction "1_1") (pintype "passive"))
      (node (ref "C3") (pin "1") (pinfunction "1_1") (pintype "passive"))
      (node (ref "C4") (pin "1") (pinfunction "1_1") (pintype "passive"))
      (node (ref "C5") (pin "1") (pinfunction "1_1") (pintype "passive"))
      (node (ref "C6") (pin "1") (pinfunction "1_1") (pintype "passive"))
      (node (ref "C7") (pin "1") (pinfunction "1_1") (pintype "passive"))
      (node (ref "C9") (pin "1") (pinfunction "1_1") (pintype "passive"))
      (node (ref "D3") (pin "1") (pinfunction "1_1") (pintype "passive"))
      (node (ref "D4") (pin "1") (pinfunction "1_1") (pintype "passive"))
      (node (ref "D5") (pin "2") (pinfunction "K_2") (pintype "passive"))
      (node (ref "D7") (pin "2") (pinfunction "E_2") (pintype "passive"))
      (node (ref "JP1") (pin "1") (pinfunction "1_1") (pintype "passive"))
      (node (ref "JP1") (pin "3") (pinfunction "3_3") (pintype "passive"))
      (node (ref "JP1") (pin "5") (pinfunction "5_5") (pintype "passive"))
      (node (ref "JP1") (pin "7") (pinfunction "7_7") (pintype "passive"))
      (node (ref "JP10") (pin "4") (pinfunction "4_4") (pintype "passive"))
      (node (ref "JP11") (pin "4") (pinfunction "4_4") (pintype "passive"))
      (node (ref "JP12") (pin "4") (pinfunction "4_4") (pintype "passive"))
      (node (ref "JP2") (pin "1") (pinfunction "1_1") (pintype "passive"))
      (node (ref "JP2") (pin "3") (pinfunction "3_3") (pintype "passive"))
      (node (ref "JP2") (pin "5") (pinfunction "5_5") (pintype "passive"))
      (node (ref "JP2") (pin "7") (pinfunction "7_7") (pintype "passive"))
      (node (ref "JP3") (pin "1") (pinfunction "1_1") (pintype "passive"))
      (node (ref "JP4") (pin "4") (pinfunction "4_4") (pintype "passive"))
      (node (ref "JP5") (pin "4") (pinfunction "4_4") (pintype "passive"))
      (node (ref "JP7") (pin "5") (pinfunction "5_5") (pintype "passive"))
      (node (ref "JP8") (pin "5") (pinfunction "5_5") (pintype "passive"))
      (node (ref "K1") (pin "2") (pinfunction "2_2") (pintype "passive"))
      (node (ref "K2") (pin "2") (pinfunction "2_2") (pintype "passive"))
      (node (ref "K3") (pin "2") (pinfunction "2_2") (pintype "passive"))
      (node (ref "K4") (pin "2") (pinfunction "2_2") (pintype "passive"))
      (node (ref "K5") (pin "2") (pinfunction "2_2") (pintype "passive"))
      (node (ref "O1") (pin "2") (pinfunction "2_2") (pintype "passive"))
      (node (ref "O1") (pin "4") (pinfunction "4_4") (pintype "passive"))
      (node (ref "R1") (pin "2") (pinfunction "2_2") (pintype "passive"))
      (node (ref "R16") (pin "1") (pinfunction "1_1") (pintype "passive"))
      (node (ref "R17") (pin "1") (pinfunction "1_1") (pintype "passive"))
      (node (ref "R20") (pin "2") (pinfunction "2_2") (pintype "passive"))
      (node (ref "R4") (pin "1") (pinfunction "1_1") (pintype "passive"))
      (node (ref "R5") (pin "1") (pinfunction "1_1") (pintype "passive"))
      (node (ref "U1") (pin "29") (pinfunction "HEAT_TAB_29") (pintype "passive"))
      (node (ref "U1") (pin "3") (pinfunction "GND_3") (pintype "passive"))
      (node (ref "U2") (pin "2") (pinfunction "GND_2") (pintype "passive"))
      (node (ref "U3") (pin "1") (pinfunction "GND_1") (pintype "passive"))
      (node (ref "U4") (pin "2") (pinfunction "GND_2") (pintype "passive"))
      (node (ref "U4") (pin "8") (pinfunction "S_8") (pintype "passive"))
      (node (ref "U5") (pin "10") (pinfunction "VSS_10") (pintype "passive"))
      (node (ref "U5") (pin "19") (pinfunction "VSSA_19") (pintype "passive"))
      (node (ref "U5") (pin "26") (pinfunction "VSS_26") (pintype "passive"))
      (node (ref "U5") (pin "49") (pinfunction "VSS_49") (pintype "passive"))
      (node (ref "U5") (pin "74") (pinfunction "VSS_74") (pintype "passive"))
      (node (ref "U5") (pin "99") (pinfunction "VSS_99") (pintype "passive"))
      (node (ref "U6") (pin "5") (pinfunction "GND_5") (pintype "passive"))
      (node (ref "USB1") (pin "1") (pinfunction "SH1_1") (pintype "passive"))
      (node (ref "USB1") (pin "2") (pinfunction "SH2_2") (pintype "passive"))
      (node (ref "USB1") (pin "3") (pinfunction "SH3_3") (pintype "passive"))
      (node (ref "USB1") (pin "4") (pinfunction "SH4_4") (pintype "passive"))
      (node (ref "USB1") (pin "A1") (pinfunction "GND_A1") (pintype "passive"))
      (node (ref "USB1") (pin "A12") (pinfunction "GND_A12") (pintype "passive"))
      (node (ref "USB1") (pin "B1") (pinfunction "GND_B1") (pintype "passive"))
      (node (ref "USB1") (pin "B12") (pinfunction "GND_B12") (pintype "passive"))
    )
    (net (code "92") (name "Net-(1-LEDK)") (class "Default")
      (node (ref "1") (pin "2") (pinfunction "LEDK_2") (pintype "passive"))
      (node (ref "R21") (pin "1") (pinfunction "1_1") (pintype "passive"))
    )
    (net (code "93") (name "Net-(C10-Pad2)") (class "Default")
      (node (ref "C10") (pin "2") (pinfunction "2_2") (pintype "passive"))
      (node (ref "U5") (pin "73") (pinfunction "VCAP_73") (pintype "passive"))
    )
    (net (code "94") (name "Net-(C12-Pad2)") (class "Default")
      (node (ref "C12") (pin "2") (pinfunction "2_2") (pintype "passive"))
      (node (ref "U5") (pin "48") (pinfunction "VCAP_48") (pintype "passive"))
    )
    (net (code "95") (name "Net-(D1-A)") (class "Default")
      (node (ref "D1") (pin "1") (pinfunction "A_1") (pintype "passive"))
      (node (ref "R2") (pin "1") (pinfunction "1_1") (pintype "passive"))
    )
    (net (code "96") (name "Net-(D2-A)") (class "Default")
      (node (ref "D2") (pin "1") (pinfunction "A_1") (pintype "passive"))
      (node (ref "R3") (pin "1") (pinfunction "1_1") (pintype "passive"))
    )
    (net (code "97") (name "Net-(D5-A)") (class "Default")
      (node (ref "D5") (pin "1") (pinfunction "A_1") (pintype "passive"))
      (node (ref "R14") (pin "1") (pinfunction "1_1") (pintype "passive"))
    )
    (net (code "98") (name "Net-(D6-A)") (class "Default")
      (node (ref "D6") (pin "1") (pinfunction "A_1") (pintype "passive"))
      (node (ref "U3") (pin "11") (pinfunction "LED_11") (pintype "passive"))
    )
    (net (code "99") (name "Net-(D6-K)") (class "Default")
      (node (ref "D6") (pin "2") (pinfunction "K_2") (pintype "passive"))
      (node (ref "R17") (pin "2") (pinfunction "2_2") (pintype "passive"))
    )
    (net (code "100") (name "Net-(D7-B)") (class "Default")
      (node (ref "D7") (pin "1") (pinfunction "B_1") (pintype "passive"))
      (node (ref "R22") (pin "1") (pinfunction "1_1") (pintype "passive"))
      (node (ref "R23") (pin "1") (pinfunction "1_1") (pintype "passive"))
    )
    (net (code "101") (name "Net-(D7-C)") (class "Default")
      (node (ref "D7") (pin "3") (pinfunction "C_3") (pintype "passive"))
      (node (ref "R21") (pin "2") (pinfunction "2_2") (pintype "passive"))
    )
    (net (code "102") (name "Net-(U1-*RST)") (class "Default")
      (node (ref "R1") (pin "1") (pinfunction "1_1") (pintype "passive"))
      (node (ref "U1") (pin "9") (pinfunction "*RST_9") (pintype "passive"))
    )
    (net (code "103") (name "Net-(U2-FB)") (class "Default")
      (node (ref "C8") (pin "1") (pinfunction "1_1") (pintype "passive"))
      (node (ref "R15") (pin "1") (pinfunction "1_1") (pintype "passive"))
      (node (ref "R16") (pin "2") (pinfunction "2_2") (pintype "passive"))
      (node (ref "U2") (pin "5") (pinfunction "FB_5") (pintype "passive"))
    )
    (net (code "104") (name "Net-(U2-LX)") (class "Default")
      (node (ref "L1") (pin "1") (pinfunction "1_1") (pintype "passive"))
      (node (ref "U2") (pin "3") (pinfunction "LX_3") (pintype "passive"))
    )
    (net (code "105") (name "Net-(U3-RESET)") (class "Default")
      (node (ref "K5") (pin "1") (pinfunction "1_1") (pintype "passive"))
      (node (ref "U3") (pin "16") (pinfunction "RESET_16") (pintype "passive"))
    )
    (net (code "106") (name "Net-(U4-VREF)") (class "Default")
      (node (ref "C13") (pin "1") (pinfunction "1_1") (pintype "passive"))
      (node (ref "R18") (pin "2") (pinfunction "2_2") (pintype "passive"))
      (node (ref "U4") (pin "5") (pinfunction "VREF_5") (pintype "passive"))
    )
    (net (code "107") (name "Net-(U5B-VDDA)") (class "Default")
      (node (ref "C18") (pin "1") (pinfunction "1_1") (pintype "passive"))
      (node (ref "L2") (pin "1") (pinfunction "1_1") (pintype "passive"))
      (node (ref "U5") (pin "20") (pinfunction "VREF+_20") (pintype "passive"))
      (node (ref "U5") (pin "21") (pinfunction "VDDA_21") (pintype "passive"))
    )
    (net (code "108") (name "Net-(USB1-CC1)") (class "Default")
      (node (ref "R5") (pin "2") (pinfunction "2_2") (pintype "passive"))
      (node (ref "USB1") (pin "A5") (pinfunction "CC1_A5") (pintype "passive"))
    )
    (net (code "109") (name "Net-(USB1-CC2)") (class "Default")
      (node (ref "R4") (pin "2") (pinfunction "2_2") (pintype "passive"))
      (node (ref "USB1") (pin "B5") (pinfunction "CC2_B5") (pintype "passive"))
    )
    (net (code "110") (name "VBUS") (class "Default")
      (node (ref "C7") (pin "2") (pinfunction "2_2") (pintype "passive"))
      (node (ref "D3") (pin "2") (pinfunction "2_2") (pintype "passive"))
      (node (ref "F1") (pin "1") (pinfunction "1_1") (pintype "passive"))
      (node (ref "JP3") (pin "2") (pinfunction "2_2") (pintype "passive"))
      (node (ref "USB1") (pin "A4") (pinfunction "VBUS_A4") (pintype "passive"))
      (node (ref "USB1") (pin "A9") (pinfunction "VBUS_A9") (pintype "passive"))
      (node (ref "USB1") (pin "B4") (pinfunction "VBUS_B4") (pintype "passive"))
      (node (ref "USB1") (pin "B9") (pinfunction "VBUS_B9") (pintype "passive"))
    )
    (net (code "111") (name "unconnected-(U1-*SUSPEND-Pad11)") (class "Default")
      (node (ref "U1") (pin "11") (pinfunction "*SUSPEND_11") (pintype "passive"))
    )
    (net (code "112") (name "unconnected-(U1-CTS-Pad23)") (class "Default")
      (node (ref "U1") (pin "23") (pinfunction "CTS_23") (pintype "passive"))
    )
    (net (code "113") (name "unconnected-(U1-DCD-Pad1)") (class "Default")
      (node (ref "U1") (pin "1") (pinfunction "DCD_1") (pintype "passive"))
    )
    (net (code "114") (name "unconnected-(U1-DSR-Pad27)") (class "Default")
      (node (ref "U1") (pin "27") (pinfunction "DSR_27") (pintype "passive"))
    )
    (net (code "115") (name "unconnected-(U1-DTR-Pad28)") (class "Default")
      (node (ref "U1") (pin "28") (pinfunction "DTR_28") (pintype "passive"))
    )
    (net (code "116") (name "unconnected-(U1-NC-Pad10)") (class "Default")
      (node (ref "U1") (pin "10") (pinfunction "NC_10") (pintype "passive"))
    )
    (net (code "117") (name "unconnected-(U1-NC-Pad13)") (class "Default")
      (node (ref "U1") (pin "13") (pinfunction "NC_13") (pintype "passive"))
    )
    (net (code "118") (name "unconnected-(U1-NC-Pad14)") (class "Default")
      (node (ref "U1") (pin "14") (pinfunction "NC_14") (pintype "passive"))
    )
    (net (code "119") (name "unconnected-(U1-NC-Pad15)") (class "Default")
      (node (ref "U1") (pin "15") (pinfunction "NC_15") (pintype "passive"))
    )
    (net (code "120") (name "unconnected-(U1-NC-Pad16)") (class "Default")
      (node (ref "U1") (pin "16") (pinfunction "NC_16") (pintype "passive"))
    )
    (net (code "121") (name "unconnected-(U1-NC-Pad17)") (class "Default")
      (node (ref "U1") (pin "17") (pinfunction "NC_17") (pintype "passive"))
    )
    (net (code "122") (name "unconnected-(U1-NC-Pad18)") (class "Default")
      (node (ref "U1") (pin "18") (pinfunction "NC_18") (pintype "passive"))
    )
    (net (code "123") (name "unconnected-(U1-NC-Pad19)") (class "Default")
      (node (ref "U1") (pin "19") (pinfunction "NC_19") (pintype "passive"))
    )
    (net (code "124") (name "unconnected-(U1-NC-Pad20)") (class "Default")
      (node (ref "U1") (pin "20") (pinfunction "NC_20") (pintype "passive"))
    )
    (net (code "125") (name "unconnected-(U1-NC-Pad21)") (class "Default")
      (node (ref "U1") (pin "21") (pinfunction "NC_21") (pintype "passive"))
    )
    (net (code "126") (name "unconnected-(U1-NC-Pad22)") (class "Default")
      (node (ref "U1") (pin "22") (pinfunction "NC_22") (pintype "passive"))
    )
    (net (code "127") (name "unconnected-(U1-RI-Pad2)") (class "Default")
      (node (ref "U1") (pin "2") (pinfunction "RI_2") (pintype "passive"))
    )
    (net (code "128") (name "unconnected-(U1-RTS-Pad24)") (class "Default")
      (node (ref "U1") (pin "24") (pinfunction "RTS_24") (pintype "passive"))
    )
    (net (code "129") (name "unconnected-(U1-SUSPEND-Pad12)") (class "Default")
      (node (ref "U1") (pin "12") (pinfunction "SUSPEND_12") (pintype "passive"))
    )
    (net (code "130") (name "unconnected-(U1-VDD-Pad6)") (class "Default")
      (node (ref "U1") (pin "6") (pinfunction "VDD_6") (pintype "passive"))
    )
    (net (code "131") (name "unconnected-(U3-KEY+-Pad10)") (class "Default")
      (node (ref "U3") (pin "10") (pinfunction "KEY+_10") (pintype "passive+no_connect"))
    )
    (net (code "132") (name "unconnected-(U3-NC-Pad5)") (class "Default")
      (node (ref "U3") (pin "5") (pinfunction "NC_5") (pintype "passive"))
    )
    (net (code "133") (name "unconnected-(U3-NC-Pad6)") (class "Default")
      (node (ref "U3") (pin "6") (pinfunction "NC_6") (pintype "passive"))
    )
    (net (code "134") (name "unconnected-(U3-NC-Pad7)") (class "Default")
      (node (ref "U3") (pin "7") (pinfunction "NC_7") (pintype "passive"))
    )
    (net (code "135") (name "unconnected-(U3-NC-Pad8)") (class "Default")
      (node (ref "U3") (pin "8") (pinfunction "NC_8") (pintype "passive"))
    )
    (net (code "136") (name "unconnected-(U3-NC-Pad13)") (class "Default")
      (node (ref "U3") (pin "13") (pinfunction "NC_13") (pintype "passive"))
    )
    (net (code "137") (name "unconnected-(U3-NC-Pad14)") (class "Default")
      (node (ref "U3") (pin "14") (pinfunction "NC_14") (pintype "passive"))
    )
    (net (code "138") (name "unconnected-(U3-NC-Pad15)") (class "Default")
      (node (ref "U3") (pin "15") (pinfunction "NC_15") (pintype "passive"))
    )
    (net (code "139") (name "unconnected-(U3-STATE-Pad9)") (class "Default")
      (node (ref "U3") (pin "9") (pinfunction "STATE_9") (pintype "passive+no_connect"))
    )
    (net (code "140") (name "unconnected-(U6-NC-Pad1)") (class "Default")
      (node (ref "U6") (pin "1") (pinfunction "NC_1") (pintype "passive"))
    )
    (net (code "141") (name "unconnected-(U6-NC-Pad6)") (class "Default")
      (node (ref "U6") (pin "6") (pinfunction "NC_6") (pintype "passive"))
    )
    (net (code "142") (name "unconnected-(U6-NC-Pad7)") (class "Default")
      (node (ref "U6") (pin "7") (pinfunction "NC_7") (pintype "passive"))
    )
    (net (code "143") (name "unconnected-(U6-NC-Pad8)") (class "Default")
      (node (ref "U6") (pin "8") (pinfunction "NC_8") (pintype "passive"))
    )
    (net (code "144") (name "unconnected-(U6-NC-Pad9)") (class "Default")
      (node (ref "U6") (pin "9") (pinfunction "NC_9") (pintype "passive"))
    )
    (net (code "145") (name "unconnected-(U6-NC-Pad10)") (class "Default")
      (node (ref "U6") (pin "10") (pinfunction "NC_10") (pintype "passive"))
    )
    (net (code "146") (name "unconnected-(U6-NC-Pad11)") (class "Default")
      (node (ref "U6") (pin "11") (pinfunction "NC_11") (pintype "passive"))
    )
    (net (code "147") (name "unconnected-(U6-NC-Pad12)") (class "Default")
      (node (ref "U6") (pin "12") (pinfunction "NC_12") (pintype "passive"))
    )
    (net (code "148") (name "unconnected-(USB1-SBU1-PadA8)") (class "Default")
      (node (ref "USB1") (pin "A8") (pinfunction "SBU1_A8") (pintype "passive+no_connect"))
    )
    (net (code "149") (name "unconnected-(USB1-SBU2-PadB8)") (class "Default")
      (node (ref "USB1") (pin "B8") (pinfunction "SBU2_B8") (pintype "passive+no_connect"))
    )
  )
)
